# BMS_Carrier_-_Current_Sense_Interface.net
KiCad netlist of a schematic drawn in Altium Designer
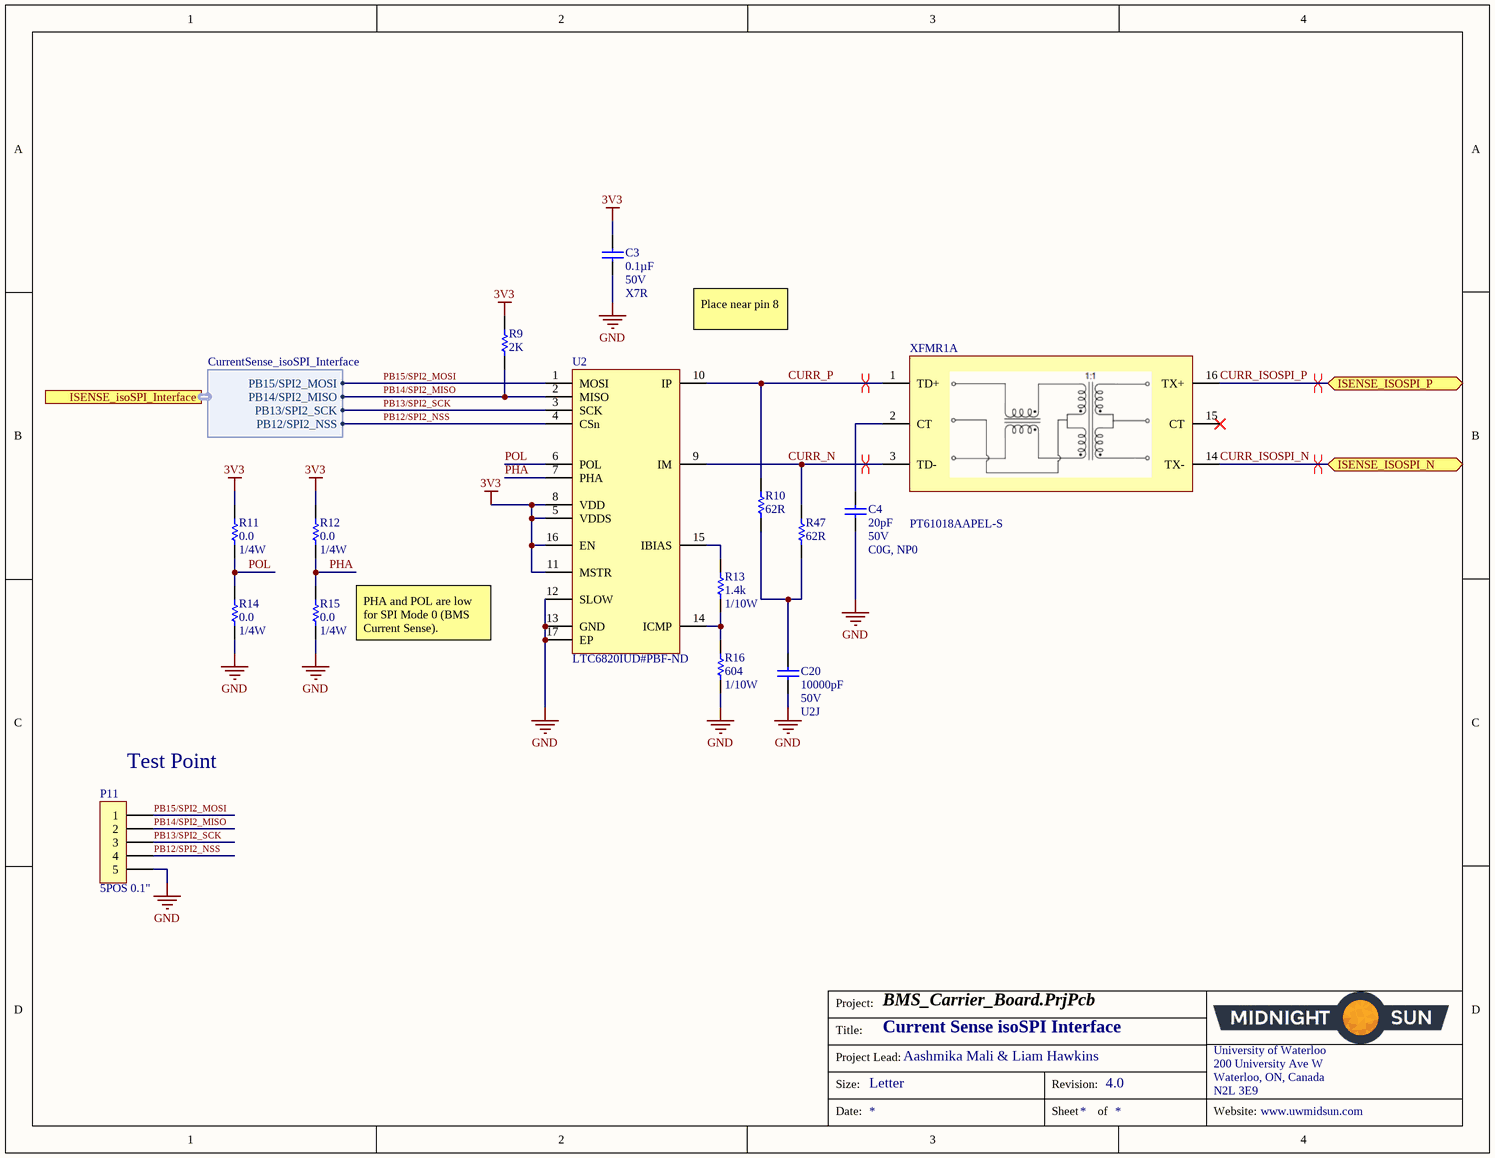
[diagram p0: BMS Carrier - Current Sense Interface.SchDoc]

(export (version "E")
  (design (tool "Eeschema 10.0.6"))
  (components
    (comp (ref "C3")
      (value "CAP CER 0.1UF 50V 10% X7R 0603")
      (footprint "CAP, 0603")
      (description "0.10µF ±10% 50V Ceramic Capacitor X7R 0603 (1608 Metric)")
      (fields
        (field (name "TOLERANCE") "±10%")
        (field (name "CAPACITANCE") "0.1µF")
        (field (name "VOLTAGE") "50V")
        (field (name "TEMPERATURE COEFFICIENT") "X7R")
      )
      (libsource (lib "Schematic Diagrams") (part "CAP CER 0.1UF 50V 10% X7R 0603"))
    )
    (comp (ref "C4")
      (value "CAP CER 20PF 50V ±5% C0G/NP0 0603")
      (footprint "CAP, 0603")
      (description "20pF ±5% 50V Ceramic Capacitor C0G, NP0 0603 (1608 Metric)")
      (fields
        (field (name "TOLERANCE") "±5%")
        (field (name "CAPACITANCE") "20pF")
        (field (name "VOLTAGE") "50V")
        (field (name "TEMPERATURE COEFFICIENT") "C0G, NP0")
      )
      (libsource (lib "Schematic Diagrams") (part "CAP CER 20PF 50V ±5% C0G/NP0 0603"))
    )
    (comp (ref "C20")
      (value "CAP CER 10nF 50V 5% X7R 0603")
      (footprint "CAP, 0603")
      (description "10000pF ±5% 50V Ceramic Capacitor U2J 0603 (1608 Metric)")
      (fields
        (field (name "TOLERANCE") "±5%")
        (field (name "CAPACITANCE") "10000pF")
        (field (name "VOLTAGE") "50V")
        (field (name "TEMPERATURE COEFFICIENT") "U2J")
      )
      (libsource (lib "Schematic Diagrams") (part "CAP CER 10nF 50V 5% X7R 0603"))
    )
    (comp (ref "P11")
      (value "5POS 0.1\"")
      (footprint "CONN, 5POS HEADR 0.1\"")
      (libsource (lib "Schematic Diagrams") (part "CONN 5POS HEADR MALE 0.1{dblquote}"))
    )
    (comp (ref "R9")
      (value "2K")
      (footprint "RES, 0603")
      (description "2k Ohm ±1% 0.1W, 1/10W Chip Resistor 0603 (1608 Metric) Moisture Resistant Thick Film")
      (fields
        (field (name "MANUFACTURER") "Yageo")
        (field (name "MANUFACTURER PART NUMBER") "RC0603FR-072KL")
      )
      (libsource (lib "Schematic Diagrams") (part "RES 2K OHM 1% 1/10W 0603"))
    )
    (comp (ref "R10")
      (value "62R")
      (footprint "RES, 0603")
      (description "62 Ohms ±0.1% 0.1W, 1/10W Chip Resistor 0603 (1608 Metric) Automotive AEC-Q200 Thin Film")
      (fields
        (field (name "MANUFACTURER") "Panasonic Electronic Components")
        (field (name "MANUFACTURER PART NUMBER") "ERA-3AEB620V")
      )
      (libsource (lib "Schematic Diagrams") (part "RES 62 OHM 0.1% 1/10W 0603"))
    )
    (comp (ref "R11")
      (value "RES 0.0 OHM 1/4W 0603")
      (footprint "RES, 0603")
      (description "RES SMD 0.0 OHM JUMPER 1/4W 0603")
      (fields (field (name "RESISTANCE") "0.0") (field (name "POWER (WATTS)") "1/4W"))
      (libsource (lib "Schematic Diagrams") (part "RES 0.0 OHM 1/4W 0603"))
    )
    (comp (ref "R12")
      (value "RES 0.0 OHM 1/4W 0603")
      (footprint "RES, 0603")
      (description "RES SMD 0.0 OHM JUMPER 1/4W 0603")
      (fields (field (name "RESISTANCE") "0.0") (field (name "POWER (WATTS)") "1/4W"))
      (libsource (lib "Schematic Diagrams") (part "RES 0.0 OHM 1/4W 0603"))
    )
    (comp (ref "R13")
      (value "RES 1.4k OHM 1% 1/10W 0603")
      (footprint "RES, 0603")
      (description "RES SMD 1.4K OHM 1% 1/10W 0603")
      (fields
        (field (name "TOLERANCE") "±1%")
        (field (name "RESISTANCE") "1.4k")
        (field (name "POWER") "1/10W")
      )
      (libsource (lib "Schematic Diagrams") (part "RES 1.4k OHM 1% 1/10W 0603"))
    )
    (comp (ref "R14")
      (value "RES 0.0 OHM 1/4W 0603")
      (footprint "RES, 0603")
      (description "RES SMD 0.0 OHM JUMPER 1/4W 0603")
      (fields (field (name "RESISTANCE") "0.0") (field (name "POWER (WATTS)") "1/4W"))
      (libsource (lib "Schematic Diagrams") (part "RES 0.0 OHM 1/4W 0603"))
    )
    (comp (ref "R15")
      (value "RES 0.0 OHM 1/4W 0603")
      (footprint "RES, 0603")
      (description "RES SMD 0.0 OHM JUMPER 1/4W 0603")
      (fields (field (name "RESISTANCE") "0.0") (field (name "POWER (WATTS)") "1/4W"))
      (libsource (lib "Schematic Diagrams") (part "RES 0.0 OHM 1/4W 0603"))
    )
    (comp (ref "R16")
      (value "RES 604 OHM 1% 1/10W 0603")
      (footprint "RES, 0603")
      (description "RES SMD 604 OHM 1% 1/10W 0603")
      (fields
        (field (name "TOLERANCE") "±1%")
        (field (name "RESISTANCE") "604")
        (field (name "POWER") "1/10W")
      )
      (libsource (lib "Schematic Diagrams") (part "RES 604 OHM 1% 1/10W 0603"))
    )
    (comp (ref "R47")
      (value "62R")
      (footprint "RES, 0603")
      (description "62 Ohms ±0.1% 0.1W, 1/10W Chip Resistor 0603 (1608 Metric) Automotive AEC-Q200 Thin Film")
      (fields
        (field (name "MANUFACTURER") "Panasonic Electronic Components")
        (field (name "MANUFACTURER PART NUMBER") "ERA-3AEB620V")
      )
      (libsource (lib "Schematic Diagrams") (part "RES 62 OHM 0.1% 1/10W 0603"))
    )
    (comp (ref "U2")
      (value "IC ISOSPI COMM INTERFACE LTC6820IUD")
      (footprint "IC COMM INTERFACE ISOSPI 16-QFN")
      (description "IC COMM INTERFACE ISOSPI 16-QFN")
      (fields
        (field (name "MANUFACTURER") "Linear Technology")
        (field (name "MANUFACTURER PART NUMBER") "LTC6820IUD#PBF")
        (field (name "SUPPLIER PART NUMBER 1") "LTC6820IUD#PBF-ND")
      )
      (libsource (lib "Schematic Diagrams") (part "IC ISOSPI COMM INTERFACE LTC6820IUD"))
    )
    (comp (ref "XFMR1")
      (value "IC PULSE XFMR 1CT:1CT 350UH SMD")
      (footprint "IC, PULSE XFMR 1CT:1CT 350UH SMD")
      (description "PULSE XFMR 1CT:1CT 350UH SMD")
      (fields (field (name "MANUFACTURER") "Bourns Inc.") (field (name "MFG_PN") "PT61018AAPEL-S"))
      (libsource (lib "Schematic Diagrams") (part "IC PULSE XFMR 1CT{colon}1CT 350UH SMD"))
    )
  )
  (nets
    (net (code "2") (name "/CURR_ISOSPI_N") (class "Default")
      (node (ref "XFMR1") (pin "14") (pinfunction "TX-_14") (pintype "passive"))
    )
    (net (code "3") (name "/CURR_ISOSPI_P") (class "Default")
      (node (ref "XFMR1") (pin "16") (pinfunction "TX+_16") (pintype "passive"))
    )
    (net (code "4") (name "/CURR_N") (class "Default")
      (node (ref "R47") (pin "1") (pinfunction "1_1") (pintype "passive"))
      (node (ref "U2") (pin "9") (pinfunction "IM_9") (pintype "passive"))
      (node (ref "XFMR1") (pin "3") (pinfunction "TD-_3") (pintype "passive"))
    )
    (net (code "5") (name "/CURR_P") (class "Default")
      (node (ref "R10") (pin "1") (pinfunction "1_1") (pintype "passive"))
      (node (ref "U2") (pin "10") (pinfunction "IP_10") (pintype "passive"))
      (node (ref "XFMR1") (pin "1") (pinfunction "TD+_1") (pintype "passive"))
    )
    (net (code "6") (name "/PB12{slash}SPI2_NSS") (class "Default")
      (node (ref "P11") (pin "4") (pinfunction "4_4") (pintype "passive"))
      (node (ref "U2") (pin "4") (pinfunction "CSn_4") (pintype "passive"))
    )
    (net (code "7") (name "/PB13{slash}SPI2_SCK") (class "Default")
      (node (ref "P11") (pin "3") (pinfunction "3_3") (pintype "passive"))
      (node (ref "U2") (pin "3") (pinfunction "SCK_3") (pintype "passive"))
    )
    (net (code "8") (name "/PB14{slash}SPI2_MISO") (class "Default")
      (node (ref "P11") (pin "2") (pinfunction "2_2") (pintype "passive"))
      (node (ref "R9") (pin "2") (pinfunction "2_2") (pintype "passive"))
      (node (ref "U2") (pin "2") (pinfunction "MISO_2") (pintype "passive"))
    )
    (net (code "9") (name "/PB15{slash}SPI2_MOSI") (class "Default")
      (node (ref "P11") (pin "1") (pinfunction "1_1") (pintype "passive"))
      (node (ref "U2") (pin "1") (pinfunction "MOSI_1") (pintype "passive"))
    )
    (net (code "10") (name "/PHA") (class "Default")
      (node (ref "R12") (pin "2") (pinfunction "2_2") (pintype "passive"))
      (node (ref "R15") (pin "1") (pinfunction "1_1") (pintype "passive"))
      (node (ref "U2") (pin "7") (pinfunction "PHA_7") (pintype "passive"))
    )
    (net (code "11") (name "/POL") (class "Default")
      (node (ref "R11") (pin "2") (pinfunction "2_2") (pintype "passive"))
      (node (ref "R14") (pin "1") (pinfunction "1_1") (pintype "passive"))
      (node (ref "U2") (pin "6") (pinfunction "POL_6") (pintype "passive"))
    )
    (net (code "13") (name "3V3") (class "Default")
      (node (ref "C3") (pin "1") (pinfunction "1_1") (pintype "passive"))
      (node (ref "R11") (pin "1") (pinfunction "1_1") (pintype "passive"))
      (node (ref "R12") (pin "1") (pinfunction "1_1") (pintype "passive"))
      (node (ref "R9") (pin "1") (pinfunction "1_1") (pintype "passive"))
      (node (ref "U2") (pin "11") (pinfunction "MSTR_11") (pintype "passive"))
      (node (ref "U2") (pin "16") (pinfunction "EN_16") (pintype "passive"))
      (node (ref "U2") (pin "5") (pinfunction "VDDS_5") (pintype "passive"))
      (node (ref "U2") (pin "8") (pinfunction "VDD_8") (pintype "passive"))
    )
    (net (code "14") (name "GND") (class "Default")
      (node (ref "C20") (pin "2") (pinfunction "2_2") (pintype "passive"))
      (node (ref "C3") (pin "2") (pinfunction "2_2") (pintype "passive"))
      (node (ref "C4") (pin "2") (pinfunction "2_2") (pintype "passive"))
      (node (ref "P11") (pin "5") (pinfunction "5_5") (pintype "passive"))
      (node (ref "R14") (pin "2") (pinfunction "2_2") (pintype "passive"))
      (node (ref "R15") (pin "2") (pinfunction "2_2") (pintype "passive"))
      (node (ref "R16") (pin "2") (pinfunction "2_2") (pintype "passive"))
      (node (ref "U2") (pin "12") (pinfunction "SLOW_12") (pintype "passive"))
      (node (ref "U2") (pin "13") (pinfunction "GND_13") (pintype "passive"))
      (node (ref "U2") (pin "17") (pinfunction "EP_17") (pintype "passive"))
    )
    (net (code "15") (name "Net-(C4-Pad1)") (class "Default")
      (node (ref "C4") (pin "1") (pinfunction "1_1") (pintype "passive"))
      (node (ref "XFMR1") (pin "2") (pinfunction "CT_2") (pintype "passive"))
    )
    (net (code "16") (name "Net-(C20-Pad1)") (class "Default")
      (node (ref "C20") (pin "1") (pinfunction "1_1") (pintype "passive"))
      (node (ref "R10") (pin "2") (pinfunction "2_2") (pintype "passive"))
      (node (ref "R47") (pin "2") (pinfunction "2_2") (pintype "passive"))
    )
    (net (code "17") (name "Net-(U2-IBIAS)") (class "Default")
      (node (ref "R13") (pin "1") (pinfunction "1_1") (pintype "passive"))
      (node (ref "U2") (pin "15") (pinfunction "IBIAS_15") (pintype "passive"))
    )
    (net (code "18") (name "Net-(U2-ICMP)") (class "Default")
      (node (ref "R13") (pin "2") (pinfunction "2_2") (pintype "passive"))
      (node (ref "R16") (pin "1") (pinfunction "1_1") (pintype "passive"))
      (node (ref "U2") (pin "14") (pinfunction "ICMP_14") (pintype "passive"))
    )
    (net (code "19") (name "unconnected-(XFMR1A-CT-Pad15)") (class "Default")
      (node (ref "XFMR1") (pin "15") (pinfunction "CT_15") (pintype "passive+no_connect"))
    )
  )
)
